# Ventilstyring.net
KiCad netlist of a schematic drawn in EAGLE
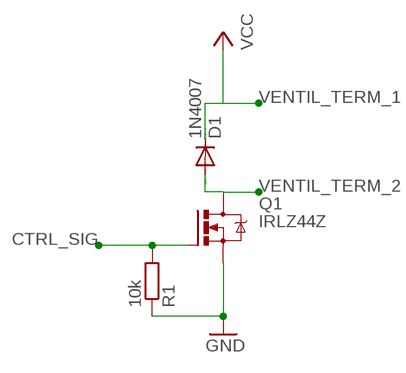
[diagram p0: schematic, sheet 1]

(export (version "E")
  (design (tool "Eeschema 10.0.6"))
  (components
    (comp (ref "D1")
      (value "1N4007")
      (footprint "eagle-import:DO41-10")
      (libsource (lib "eagle-import") (part "1N4004"))
    )
    (comp (ref "Q1")
      (value "IRLZ44Z")
      (footprint "eagle-import:TO220BH")
      (libsource (lib "eagle-import") (part "IRLZ44Z"))
    )
    (comp (ref "R1")
      (value "10k")
      (footprint "eagle-import:0204V")
      (libsource (lib "eagle-import") (part "R-EU_0204/2V"))
    )
  )
  (nets
    (net (code "1") (name "/CTRL_SIG") (class "Default")
      (node (ref "Q1") (pin "G") (pinfunction "G_G") (pintype "passive"))
      (node (ref "R1") (pin "2") (pinfunction "2_2") (pintype "passive"))
    )
    (net (code "2") (name "/VENTIL_TERM_2") (class "Default")
      (node (ref "D1") (pin "A") (pinfunction "A_A") (pintype "passive"))
      (node (ref "Q1") (pin "D") (pinfunction "D_D") (pintype "passive"))
    )
    (net (code "3") (name "GND") (class "Default")
      (node (ref "Q1") (pin "S") (pinfunction "S_S") (pintype "passive"))
      (node (ref "R1") (pin "1") (pinfunction "1_1") (pintype "passive"))
    )
    (net (code "4") (name "VCC") (class "Default")
      (node (ref "D1") (pin "C") (pinfunction "C_C") (pintype "passive"))
    )
  )
)
